# avr-usb-ptt.net
KiCad netlist of a schematic drawn in EAGLE
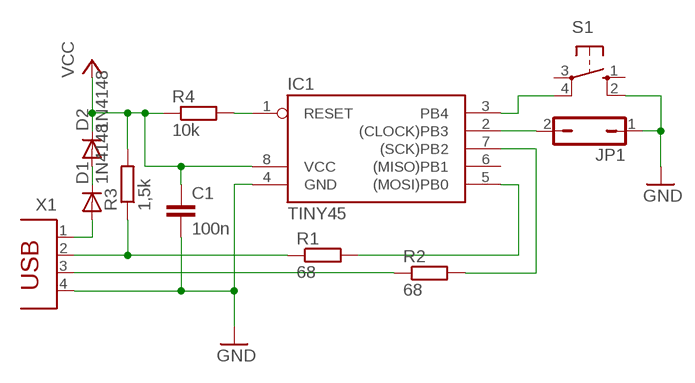
[diagram p0: schematic, sheet 1]

(export (version "E")
  (design (tool "Eeschema 10.0.6"))
  (components
    (comp (ref "C1")
      (value "100n")
      (footprint "eagle-import:C050-024X044")
      (libsource (lib "eagle-import") (part "C-EU050-024X044"))
    )
    (comp (ref "D1")
      (value "1N4148")
      (footprint "eagle-import:DO35-7")
      (libsource (lib "eagle-import") (part "1N4148DO35-7"))
    )
    (comp (ref "D2")
      (value "1N4148")
      (footprint "eagle-import:DO35-7")
      (libsource (lib "eagle-import") (part "1N4148DO35-7"))
    )
    (comp (ref "IC1")
      (value "TINY45")
      (footprint "eagle-import:DIL08")
      (libsource (lib "eagle-import") (part "TINY22P"))
    )
    (comp (ref "JP1")
      (value "JP1Q")
      (footprint "eagle-import:JP1")
      (libsource (lib "eagle-import") (part "JP1Q"))
    )
    (comp (ref "R1")
      (value "68")
      (footprint "eagle-import:0207_10")
      (libsource (lib "eagle-import") (part "R-EU_0207/10"))
    )
    (comp (ref "R2")
      (value "68")
      (footprint "eagle-import:0207_10")
      (libsource (lib "eagle-import") (part "R-EU_0207/10"))
    )
    (comp (ref "R3")
      (value "1,5k")
      (footprint "eagle-import:0207_10")
      (libsource (lib "eagle-import") (part "R-EU_0207/10"))
    )
    (comp (ref "R4")
      (value "10k")
      (footprint "eagle-import:0207_10")
      (libsource (lib "eagle-import") (part "R-EU_0207/10"))
    )
    (comp (ref "S1")
      (value "10-XX")
      (footprint "eagle-import:B3F-10XX")
      (fields (field (name "MPN") "B3F-1000"))
      (libsource (lib "eagle-import") (part "10-XX"))
    )
    (comp (ref "X1")
      (value "PN61729")
      (footprint "eagle-import:PN61729")
      (libsource (lib "eagle-import") (part "PN61729"))
    )
  )
  (nets
    (net (code "1") (name "GND") (class "Default")
      (node (ref "C1") (pin "2") (pinfunction "2_2") (pintype "passive"))
      (node (ref "IC1") (pin "4") (pinfunction "GND_4") (pintype "power_in"))
      (node (ref "JP1") (pin "1") (pinfunction "1_1") (pintype "passive"))
      (node (ref "S1") (pin "2") (pinfunction "S1_2") (pintype "passive"))
      (node (ref "X1") (pin "4") (pinfunction "4_4") (pintype "passive"))
    )
    (net (code "2") (name "Net-(D1-PadA)") (class "Default")
      (node (ref "D1") (pin "A") (pinfunction "A_A") (pintype "passive"))
      (node (ref "X1") (pin "1") (pinfunction "1_1") (pintype "passive"))
    )
    (net (code "3") (name "Net-(D1-PadC)") (class "Default")
      (node (ref "D1") (pin "C") (pinfunction "C_C") (pintype "passive"))
      (node (ref "D2") (pin "A") (pinfunction "A_A") (pintype "passive"))
    )
    (net (code "4") (name "Net-(IC1-(CLOCK)PB3)") (class "Default")
      (node (ref "IC1") (pin "2") (pinfunction "(CLOCK)PB3_2") (pintype "bidirectional"))
      (node (ref "JP1") (pin "2") (pinfunction "2_2") (pintype "passive"))
    )
    (net (code "5") (name "Net-(IC1-(MOSI)PB0)") (class "Default")
      (node (ref "IC1") (pin "5") (pinfunction "(MOSI)PB0_5") (pintype "bidirectional"))
      (node (ref "R1") (pin "2") (pinfunction "2_2") (pintype "passive"))
    )
    (net (code "6") (name "Net-(IC1-(SCK)PB2)") (class "Default")
      (node (ref "IC1") (pin "7") (pinfunction "(SCK)PB2_7") (pintype "bidirectional"))
      (node (ref "R2") (pin "2") (pinfunction "2_2") (pintype "passive"))
    )
    (net (code "7") (name "Net-(IC1-PB4)") (class "Default")
      (node (ref "IC1") (pin "3") (pinfunction "PB4_3") (pintype "bidirectional"))
      (node (ref "S1") (pin "4") (pinfunction "P1_4") (pintype "passive"))
    )
    (net (code "8") (name "Net-(IC1-RESET)") (class "Default")
      (node (ref "IC1") (pin "1") (pinfunction "RESET_1") (pintype "input"))
      (node (ref "R4") (pin "2") (pinfunction "2_2") (pintype "passive"))
    )
    (net (code "9") (name "Net-(R1-Pad1)") (class "Default")
      (node (ref "R1") (pin "1") (pinfunction "1_1") (pintype "passive"))
      (node (ref "R3") (pin "1") (pinfunction "1_1") (pintype "passive"))
      (node (ref "X1") (pin "2") (pinfunction "2_2") (pintype "passive"))
    )
    (net (code "10") (name "Net-(R2-Pad1)") (class "Default")
      (node (ref "R2") (pin "1") (pinfunction "1_1") (pintype "passive"))
      (node (ref "X1") (pin "3") (pinfunction "3_3") (pintype "passive"))
    )
    (net (code "11") (name "VCC") (class "Default")
      (node (ref "C1") (pin "1") (pinfunction "1_1") (pintype "passive"))
      (node (ref "D2") (pin "C") (pinfunction "C_C") (pintype "passive"))
      (node (ref "IC1") (pin "8") (pinfunction "VCC_8") (pintype "power_in"))
      (node (ref "R3") (pin "2") (pinfunction "2_2") (pintype "passive"))
      (node (ref "R4") (pin "1") (pinfunction "1_1") (pintype "passive"))
    )
    (net (code "12") (name "unconnected-(IC1-(MISO)PB1-Pad6)") (class "Default")
      (node (ref "IC1") (pin "6") (pinfunction "(MISO)PB1_6") (pintype "bidirectional"))
    )
    (net (code "13") (name "unconnected-(S1-P-Pad3)") (class "Default")
      (node (ref "S1") (pin "3") (pinfunction "P_3") (pintype "passive"))
    )
    (net (code "14") (name "unconnected-(S1-S-Pad1)") (class "Default")
      (node (ref "S1") (pin "1") (pinfunction "S_1") (pintype "passive"))
    )
  )
)
